# 3V3_5V.net
KiCad netlist of a schematic drawn in Altium Designer
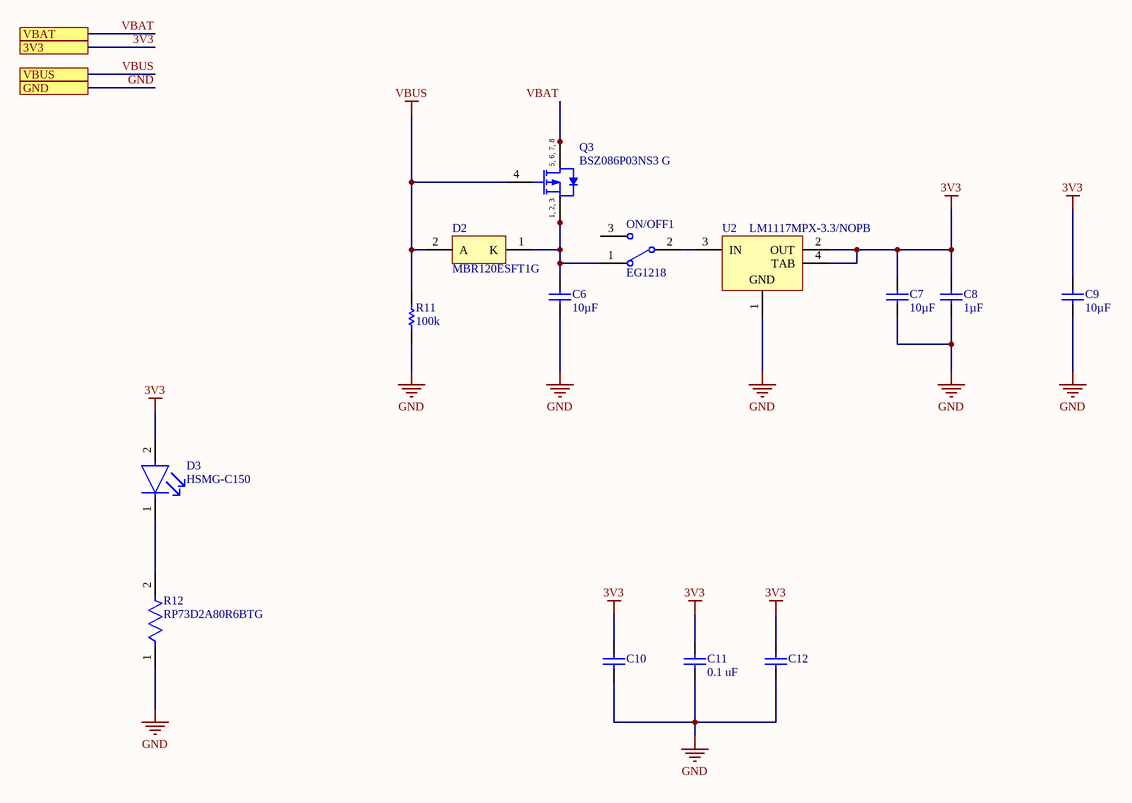
[diagram p0: 3V3_5V.SchDoc]

(export (version "E")
  (design (tool "Eeschema 10.0.6"))
  (components
    (comp (ref "C6")
      (value "10µF")
      (footprint "CAPC2013X140X50ML20T25")
      (description "10µF ±10% 16V Ceramic Capacitor X5R 0805 (2012 Metric)")
      (fields (field (name "PART NUMBER") "CL21A106KOQNNNG"))
      (libsource (lib "Altium Content Vault") (part "CAP"))
    )
    (comp (ref "C7")
      (value "10µF")
      (footprint "CAPC2013X140X50ML20T25")
      (description "10µF ±10% 16V Ceramic Capacitor X5R 0805 (2012 Metric)")
      (fields (field (name "PART NUMBER") "CL21A106KOQNNNG"))
      (libsource (lib "Altium Content Vault") (part "CAP"))
    )
    (comp (ref "C8")
      (value "1µF")
      (footprint "CAPC2013X145X50ML20T25")
      (description "1µF ±10% 16V Ceramic Capacitor X7R 0805 (2012 Metric)")
      (fields (field (name "MANUFACTURER") "Kemet") (field (name "PART NUMBER") "C0805C105K4RAC7800"))
      (libsource (lib "Altium Content Vault") (part "CAP"))
    )
    (comp (ref "C9")
      (value "10µF")
      (footprint "CAPC2013X140X50ML20T25")
      (description "10µF ±10% 16V Ceramic Capacitor X5R 0805 (2012 Metric)")
      (fields (field (name "PART NUMBER") "CL21A106KOQNNNG"))
      (libsource (lib "Altium Content Vault") (part "CAP"))
    )
    (comp (ref "C10")
      (value "C0805C106K4PACTU")
      (footprint "CAPC2013X140X50ML20T25")
      (description "10µF ±10% 16V Ceramic Capacitor X5R 0805 (2012 Metric)")
      (fields (field (name "PART NUMBER") "CL21A106KOQNNNG"))
      (libsource (lib "Altium Content Vault") (part "CAP"))
    )
    (comp (ref "C11")
      (value "0.1 uF")
      (footprint "CAPC2013X94X50ML20T25")
      (description "Chip Capacitor, Ceramic, 0.1 uF, 10%, 50 V, 0805, RoHS, Tape and Reel")
      (fields (field (name "MANUFACTURER") "AVX"))
      (libsource (lib "Altium Content Vault") (part "CAP-NP-2"))
    )
    (comp (ref "C12")
      (value "C0805C106K4PACTU")
      (footprint "CAPC2013X140X50ML20T25")
      (description "10µF ±10% 16V Ceramic Capacitor X5R 0805 (2012 Metric)")
      (fields (field (name "PART NUMBER") "CL21A106KOQNNNG"))
      (libsource (lib "Altium Content Vault") (part "CAP"))
    )
    (comp (ref "D2")
      (value "MBR120ESFT1G")
      (footprint "ONSC-SOD-123FL-2-498_V")
      (description "Schottky Power Rectifier, 2-Pin SOD-123, Pb-Free, Tape and Reel")
      (fields (field (name "MANUFACTURER") "On Semiconductor"))
      (libsource (lib "Altium Content Vault") (part "ONSC-D-K1A2-2_A"))
    )
    (comp (ref "D3")
      (value "HSMG-C150")
      (footprint "FP-HSMG-C150-MFG")
      (description "LED GREEN DIFFUSED 1206 SMD")
      (fields
        (field (name "MANUFACTURER") "Broadcom")
        (field (name "OCTOPART") "https://octopart.com/hsmg-c150-broadcom-71131304")
      )
      (libsource (lib "Altium Content Vault") (part "8706943c75ba83719d021d2fdc84c58"))
    )
    (comp (ref "ON/OFF1")
      (value "EG1218")
      (footprint "ESWI-EG1218_V")
      (description "Slide Switch, 500 V, -20 to 70 degC, 3-Pin THD, RoHS")
      (libsource (lib "Altium Content Vault") (part "SW-SPDT-3_B"))
    )
    (comp (ref "Q3")
      (value "BSZ086P03NS3 G")
      (footprint "INF-PG-TSDSON-8-1_V")
      (fields (field (name "MANUFACTURER") "Infineon"))
      (libsource (lib "Altium Content Vault") (part "INF-PEMOS-SSSGDDDD-8"))
    )
    (comp (ref "R11")
      (value "100k")
      (footprint "RESC2013X60X40ML20T25")
      (description "100 kOhms ±0.1% 0.125W, 1/8W Chip Resistor 0805 (2012 Metric) Automotive AEC-Q200 Thin Film")
      (fields (field (name "PART NUMBER") "ERA6AEB104V") (field (name "MANUFACTURER") "Panasonic"))
      (libsource (lib "Altium Content Vault") (part "RES"))
    )
    (comp (ref "R12")
      (value "RP73D2A80R6BTG")
      (footprint "FP-RP732A-MFG")
      (description "RESISTOR, 0805 80.6Ω, 0.1% 15ppm/°C")
      (fields
        (field (name "OCTOPART") "https://octopart.com/rp73d2a80r6btg-te+connectivity-42011633")
        (field (name "MANUFACTURER") "TE Connectivity")
      )
      (libsource (lib "Altium Content Vault") (part "1029c3af85768c4190bb7ad29bc67b5"))
    )
    (comp (ref "U2")
      (value "LM1117MPX-3.3/NOPB")
      (footprint "DCY0004A_M")
      (description "800mA Low-Dropout Linear Regulator, 4-pin SOT-223, Pb-Free")
      (fields (field (name "MANUFACTURER") "Texas Instruments"))
      (libsource (lib "Altium Content Vault") (part "PM-REG-LM1086-SOT4"))
    )
  )
  (nets
    (net (code "1") (name "/VBAT") (class "Default")
      (node (ref "Q3") (pin "5") (pinfunction "DRAIN_5") (pintype "passive"))
      (node (ref "Q3") (pin "6") (pinfunction "DRAIN_6") (pintype "passive"))
      (node (ref "Q3") (pin "7") (pinfunction "DRAIN_7") (pintype "passive"))
      (node (ref "Q3") (pin "8") (pinfunction "DRAIN_8") (pintype "passive"))
    )
    (net (code "2") (name "3V3") (class "Default")
      (node (ref "C10") (pin "2") (pinfunction "2_2") (pintype "passive"))
      (node (ref "C11") (pin "2") (pinfunction "2_2") (pintype "passive"))
      (node (ref "C12") (pin "2") (pinfunction "2_2") (pintype "passive"))
      (node (ref "C7") (pin "2") (pinfunction "2_2") (pintype "passive"))
      (node (ref "C8") (pin "2") (pinfunction "2_2") (pintype "passive"))
      (node (ref "C9") (pin "2") (pinfunction "2_2") (pintype "passive"))
      (node (ref "D3") (pin "2") (pinfunction "A_2") (pintype "passive"))
      (node (ref "U2") (pin "2") (pinfunction "OUT_2") (pintype "power_in"))
      (node (ref "U2") (pin "4") (pinfunction "TAB_4") (pintype "power_in"))
    )
    (net (code "3") (name "GND") (class "Default")
      (node (ref "C10") (pin "1") (pinfunction "1_1") (pintype "passive"))
      (node (ref "C11") (pin "1") (pinfunction "1_1") (pintype "passive"))
      (node (ref "C12") (pin "1") (pinfunction "1_1") (pintype "passive"))
      (node (ref "C6") (pin "1") (pinfunction "1_1") (pintype "passive"))
      (node (ref "C7") (pin "1") (pinfunction "1_1") (pintype "passive"))
      (node (ref "C8") (pin "1") (pinfunction "1_1") (pintype "passive"))
      (node (ref "C9") (pin "1") (pinfunction "1_1") (pintype "passive"))
      (node (ref "R11") (pin "1") (pinfunction "1_1") (pintype "passive"))
      (node (ref "R12") (pin "1") (pinfunction "1_1") (pintype "passive"))
      (node (ref "U2") (pin "1") (pinfunction "GND_1") (pintype "power_in"))
    )
    (net (code "4") (name "Net-(D2-K)") (class "Default")
      (node (ref "C6") (pin "2") (pinfunction "2_2") (pintype "passive"))
      (node (ref "D2") (pin "1") (pinfunction "K_1") (pintype "passive"))
      (node (ref "ON/OFF1") (pin "1") (pinfunction "1_1") (pintype "passive"))
      (node (ref "Q3") (pin "1") (pinfunction "SOURCE_1") (pintype "passive"))
      (node (ref "Q3") (pin "2") (pinfunction "SOURCE_2") (pintype "passive"))
      (node (ref "Q3") (pin "3") (pinfunction "SOURCE_3") (pintype "passive"))
    )
    (net (code "5") (name "Net-(D3-C)") (class "Default")
      (node (ref "D3") (pin "1") (pinfunction "C_1") (pintype "passive"))
      (node (ref "R12") (pin "2") (pinfunction "2_2") (pintype "passive"))
    )
    (net (code "6") (name "Net-(ON/OFF1-COM)") (class "Default")
      (node (ref "ON/OFF1") (pin "2") (pinfunction "COM_2") (pintype "passive"))
      (node (ref "U2") (pin "3") (pinfunction "IN_3") (pintype "power_in"))
    )
    (net (code "7") (name "VBUS") (class "Default")
      (node (ref "D2") (pin "2") (pinfunction "A_2") (pintype "passive"))
      (node (ref "Q3") (pin "4") (pinfunction "GATE_4") (pintype "passive"))
      (node (ref "R11") (pin "2") (pinfunction "2_2") (pintype "passive"))
    )
    (net (code "8") (name "unconnected-(ON/OFF1-Pad3)") (class "Default")
      (node (ref "ON/OFF1") (pin "3") (pinfunction "3_3") (pintype "passive"))
    )
  )
)
